# stem.net
KiCad netlist of a schematic drawn in EAGLE
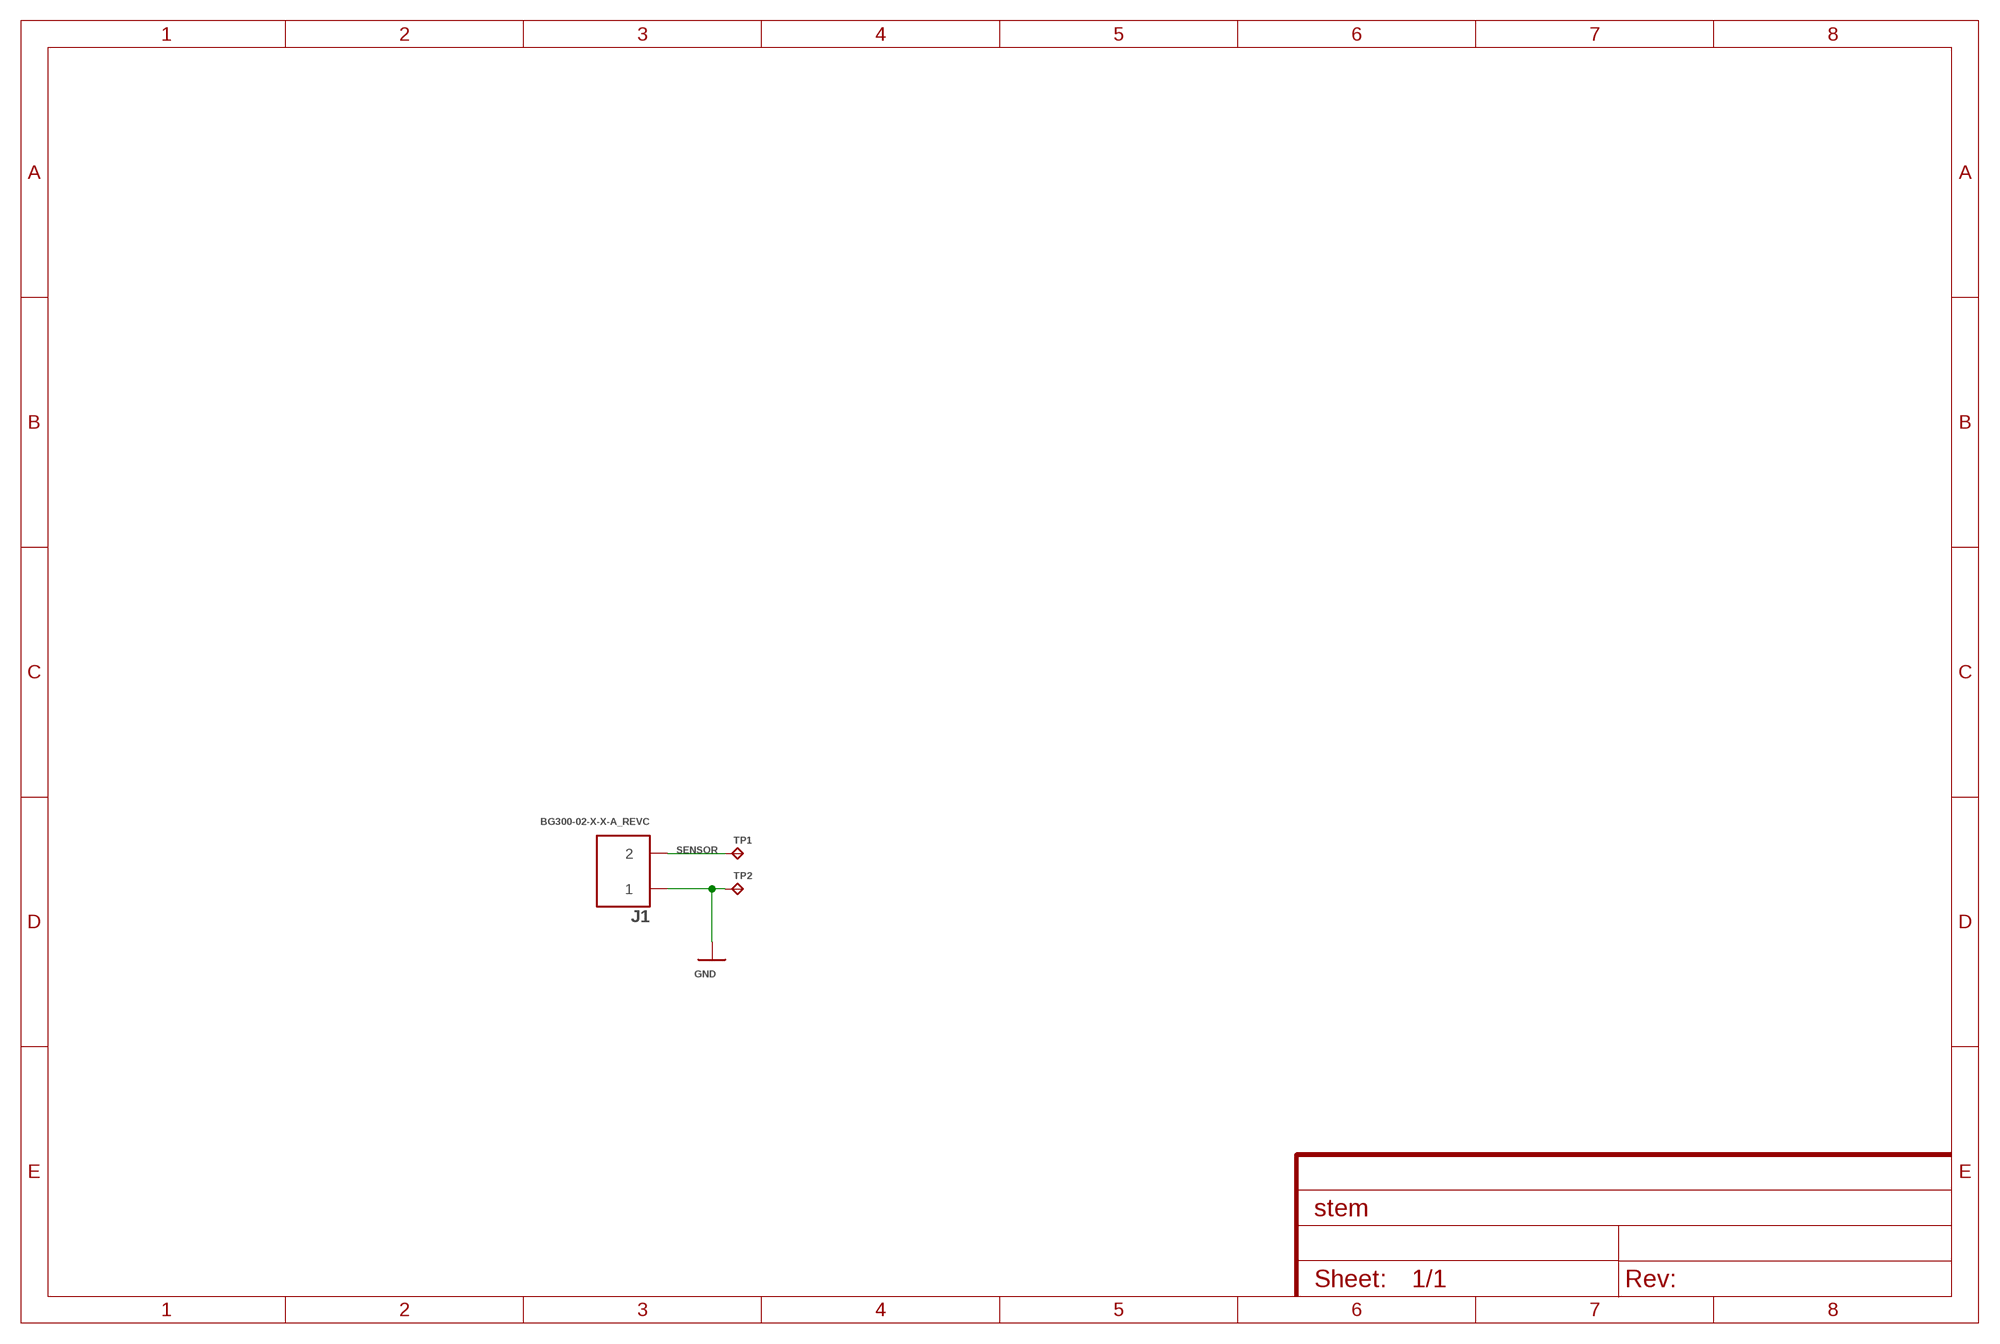
[diagram p0: schematic, sheet 1]

(export (version "E")
  (design (tool "Eeschema 10.0.6"))
  (components
    (comp (ref "J1")
      (value "BG300-02-X-X-A_REVC")
      (footprint "eagle-import:GCT_BG300-02-X-X-A_REVC")
      (fields (field (name "MF") "Global Connector Technology") (field (name "MP") "BG300-02-A-L-A"))
      (libsource (lib "eagle-import") (part "BG300-02-X-X-A_REVC"))
    )
    (comp (ref "TP1")
      (value "TPB1,27")
      (footprint "eagle-import:B1,27")
      (libsource (lib "eagle-import") (part "TPB1,27"))
    )
    (comp (ref "TP2")
      (value "TPB1,27")
      (footprint "eagle-import:B1,27")
      (libsource (lib "eagle-import") (part "TPB1,27"))
    )
  )
  (nets
    (net (code "1") (name "/SENSOR") (class "Default")
      (node (ref "J1") (pin "2") (pinfunction "2_2") (pintype "passive"))
      (node (ref "TP1") (pin "TP") (pinfunction "TP_TP") (pintype "input"))
    )
    (net (code "2") (name "GND") (class "Default")
      (node (ref "J1") (pin "1") (pinfunction "1_1") (pintype "passive"))
      (node (ref "TP2") (pin "TP") (pinfunction "TP_TP") (pintype "input"))
    )
  )
)
